# pickup3.net
KiCad netlist of a schematic drawn in EasyEDA
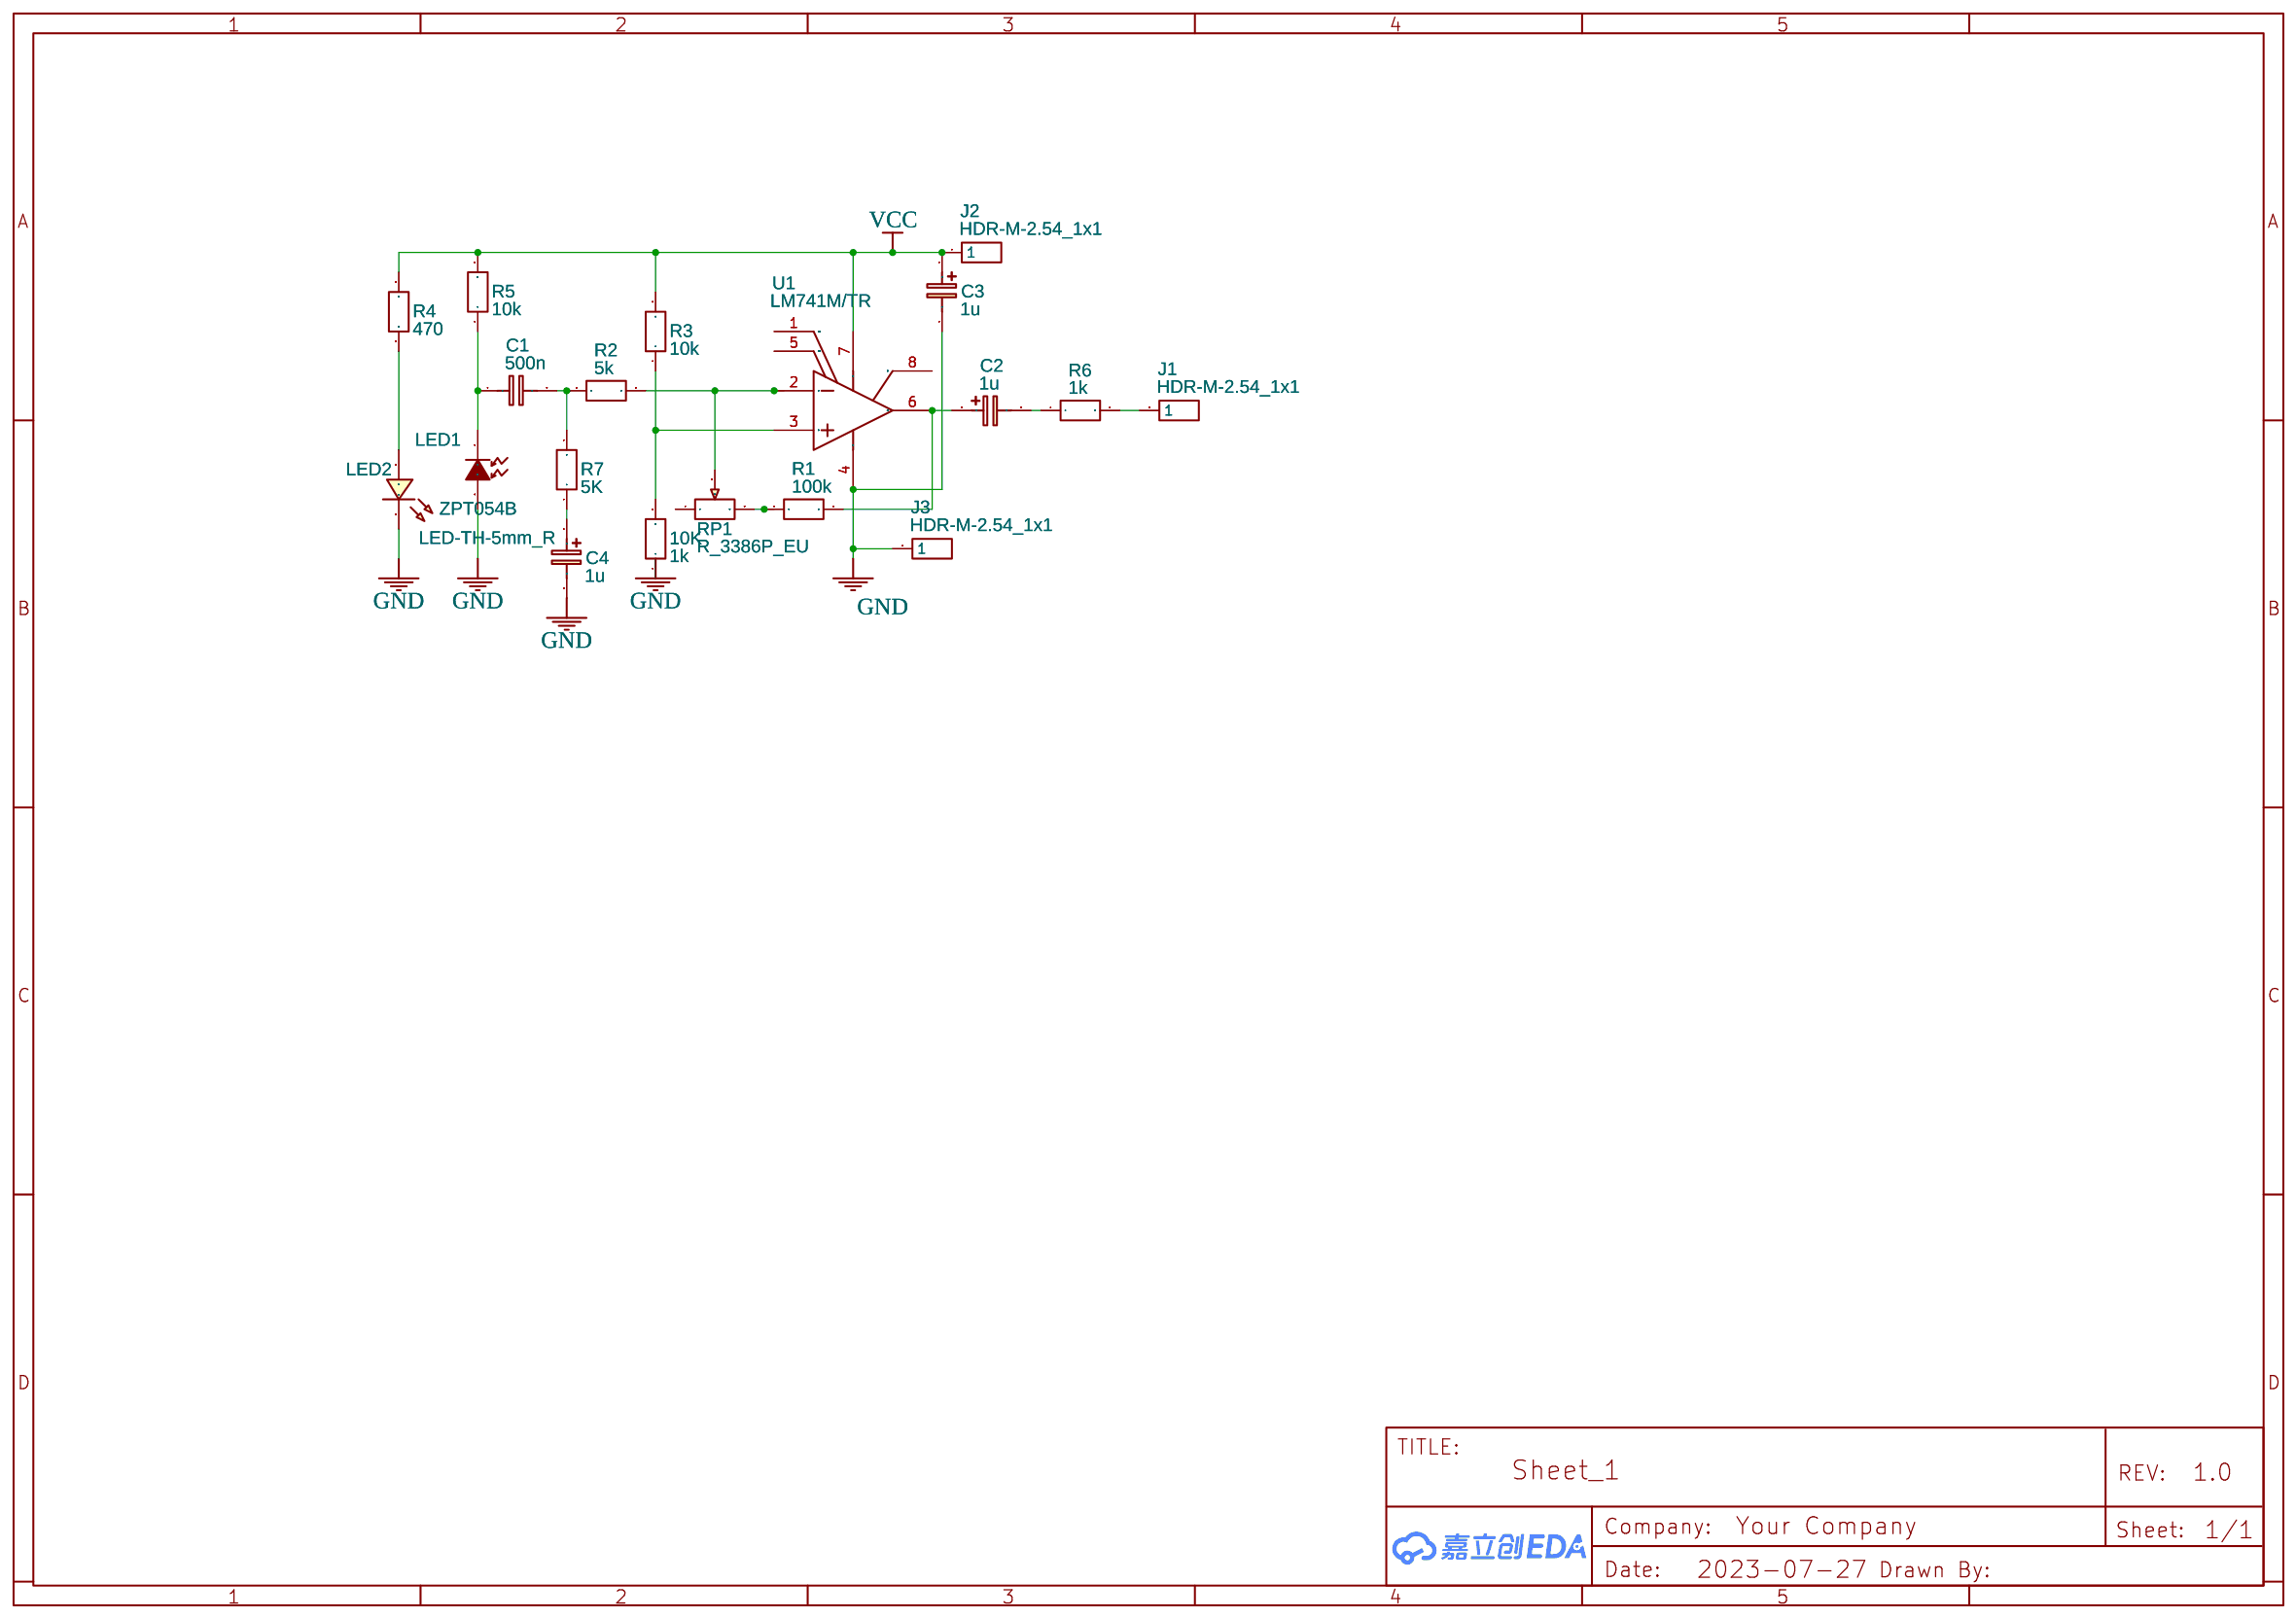
[diagram p0: schematic sheet]

(export (version "E")
  (design (tool "Eeschema 10.0.6"))
  (components
    (comp (ref "10K") (value "1k") (libsource (lib "") (part "R_0603_EU_2")))
    (comp (ref "C1") (value "500n") (libsource (lib "") (part "C_0603_EU")))
    (comp (ref "C2") (value "1u") (libsource (lib "") (part "C_Tan_SMD_A_EU_1")))
    (comp (ref "C3") (value "1u") (libsource (lib "") (part "C_Tan_SMD_A_EU")))
    (comp (ref "C4") (value "1u") (libsource (lib "") (part "C_Tan_SMD_A_EU")))
    (comp (ref "J1")
      (value "HDR-M-2.54_1x1")
      (fields (field (name "BOM_Supplier Part") "C81276"))
      (libsource (lib "") (part "HDR-M-2.54_1x1"))
    )
    (comp (ref "J2")
      (value "HDR-M-2.54_1x1")
      (fields (field (name "BOM_Supplier Part") "C81276"))
      (libsource (lib "") (part "HDR-M-2.54_1x1"))
    )
    (comp (ref "J3")
      (value "HDR-M-2.54_1x1")
      (fields (field (name "BOM_Supplier Part") "C81276"))
      (libsource (lib "") (part "HDR-M-2.54_1x1"))
    )
    (comp (ref "LED1")
      (value "ZPT054B")
      (fields (field (name "Manufacturer") "Chau Light"))
      (libsource (lib "") (part "ZPT054B"))
    )
    (comp (ref "LED2")
      (value "LED-TH-5mm_R")
      (fields
        (field (name "BOM_Manufacturer Part") "333-2SURD/S530-A3")
        (field (name "BOM_Supplier Part") "C87271")
      )
      (libsource (lib "") (part "LED-TH-5mm_R"))
    )
    (comp (ref "R1") (value "100k") (libsource (lib "") (part "R_0603_EU_1")))
    (comp (ref "R2") (value "5k") (libsource (lib "") (part "R_0603_EU_1")))
    (comp (ref "R3") (value "10k") (libsource (lib "") (part "R_0603_EU")))
    (comp (ref "R4") (value "470") (libsource (lib "") (part "R_0603_EU")))
    (comp (ref "R5") (value "10k") (libsource (lib "") (part "R_0603_EU")))
    (comp (ref "R6") (value "1k") (libsource (lib "") (part "R_0603_EU_1")))
    (comp (ref "R7") (value "5K") (libsource (lib "") (part "R_0603_EU")))
    (comp (ref "RP1") (value "R_3386P_EU") (libsource (lib "") (part "R_3386P_EU")))
    (comp (ref "U1")
      (value "LM741M/TR")
      (fields (field (name "Manufacturer") "HGSEMI(华冠)"))
      (libsource (lib "") (part "LM741M/TR"))
    )
  )
  (nets
    (net (code "1") (name "GND") (class "Default")
      (node (ref "10K") (pin "1") (pinfunction "1_1") (pintype "unspecified"))
      (node (ref "C3") (pin "2") (pinfunction "2_2") (pintype "unspecified"))
      (node (ref "C4") (pin "2") (pinfunction "2_2") (pintype "unspecified"))
      (node (ref "J3") (pin "1") (pinfunction "1_1") (pintype "input"))
      (node (ref "LED1") (pin "2") (pinfunction "C_2") (pintype "input"))
      (node (ref "LED2") (pin "2") (pinfunction "2_2") (pintype "unspecified"))
      (node (ref "U1") (pin "4") (pinfunction "V-_4") (pintype "passive"))
    )
    (net (code "2") (name "Net-(C1-Pad2)") (class "Default")
      (node (ref "C1") (pin "2") (pinfunction "2_2") (pintype "unspecified"))
      (node (ref "R2") (pin "1") (pinfunction "1_1") (pintype "unspecified"))
      (node (ref "R7") (pin "2") (pinfunction "2_2") (pintype "unspecified"))
    )
    (net (code "3") (name "Net-(C2-Pad2)") (class "Default")
      (node (ref "C2") (pin "2") (pinfunction "2_2") (pintype "unspecified"))
      (node (ref "R6") (pin "1") (pinfunction "1_1") (pintype "unspecified"))
    )
    (net (code "4") (name "Net-(C4-Pad1)") (class "Default")
      (node (ref "C4") (pin "1") (pinfunction "1_1") (pintype "unspecified"))
      (node (ref "R7") (pin "1") (pinfunction "1_1") (pintype "unspecified"))
    )
    (net (code "5") (name "Net-(J1-Pad1)") (class "Default")
      (node (ref "J1") (pin "1") (pinfunction "1_1") (pintype "input"))
      (node (ref "R6") (pin "2") (pinfunction "2_2") (pintype "unspecified"))
    )
    (net (code "6") (name "Net-(LED1-E)") (class "Default")
      (node (ref "C1") (pin "1") (pinfunction "1_1") (pintype "unspecified"))
      (node (ref "LED1") (pin "1") (pinfunction "E_1") (pintype "input"))
      (node (ref "R5") (pin "1") (pinfunction "1_1") (pintype "unspecified"))
    )
    (net (code "7") (name "Net-(LED2-Pad1)") (class "Default")
      (node (ref "LED2") (pin "1") (pinfunction "1_1") (pintype "unspecified"))
      (node (ref "R4") (pin "1") (pinfunction "1_1") (pintype "unspecified"))
    )
    (net (code "8") (name "Net-(R1-Pad1)") (class "Default")
      (node (ref "R1") (pin "1") (pinfunction "1_1") (pintype "unspecified"))
      (node (ref "RP1") (pin "3") (pinfunction "3_3") (pintype "input"))
    )
    (net (code "9") (name "Net-(U1-IN+)") (class "Default")
      (node (ref "10K") (pin "2") (pinfunction "2_2") (pintype "unspecified"))
      (node (ref "R3") (pin "1") (pinfunction "1_1") (pintype "unspecified"))
      (node (ref "U1") (pin "3") (pinfunction "IN+_3") (pintype "unspecified"))
    )
    (net (code "10") (name "Net-(U1-IN-)") (class "Default")
      (node (ref "R2") (pin "2") (pinfunction "2_2") (pintype "unspecified"))
      (node (ref "RP1") (pin "2") (pinfunction "2_2") (pintype "input"))
      (node (ref "U1") (pin "2") (pinfunction "IN-_2") (pintype "unspecified"))
    )
    (net (code "11") (name "Net-(U1-OUT)") (class "Default")
      (node (ref "C2") (pin "1") (pinfunction "1_1") (pintype "unspecified"))
      (node (ref "R1") (pin "2") (pinfunction "2_2") (pintype "unspecified"))
      (node (ref "U1") (pin "6") (pinfunction "OUT_6") (pintype "output"))
    )
    (net (code "12") (name "VCC") (class "Default")
      (node (ref "C3") (pin "1") (pinfunction "1_1") (pintype "unspecified"))
      (node (ref "J2") (pin "1") (pinfunction "1_1") (pintype "input"))
      (node (ref "R3") (pin "2") (pinfunction "2_2") (pintype "unspecified"))
      (node (ref "R4") (pin "2") (pinfunction "2_2") (pintype "unspecified"))
      (node (ref "R5") (pin "2") (pinfunction "2_2") (pintype "unspecified"))
      (node (ref "U1") (pin "7") (pinfunction "V+_7") (pintype "passive"))
    )
    (net (code "13") (name "unconnected-(RP1-Pad1)") (class "Default")
      (node (ref "RP1") (pin "1") (pinfunction "1_1") (pintype "input"))
    )
    (net (code "14") (name "unconnected-(U1-NC-Pad8)") (class "Default")
      (node (ref "U1") (pin "8") (pinfunction "NC_8") (pintype "unspecified"))
    )
    (net (code "15") (name "unconnected-(U1-OFFSET_NULL-Pad1)") (class "Default")
      (node (ref "U1") (pin "1") (pinfunction "OFFSET_NULL_1") (pintype "unspecified"))
    )
    (net (code "16") (name "unconnected-(U1-OFFSET_NULL-Pad5)") (class "Default")
      (node (ref "U1") (pin "5") (pinfunction "OFFSET_NULL_5") (pintype "unspecified"))
    )
  )
)
